# Un_GPS.net
KiCad netlist of a schematic drawn in EAGLE
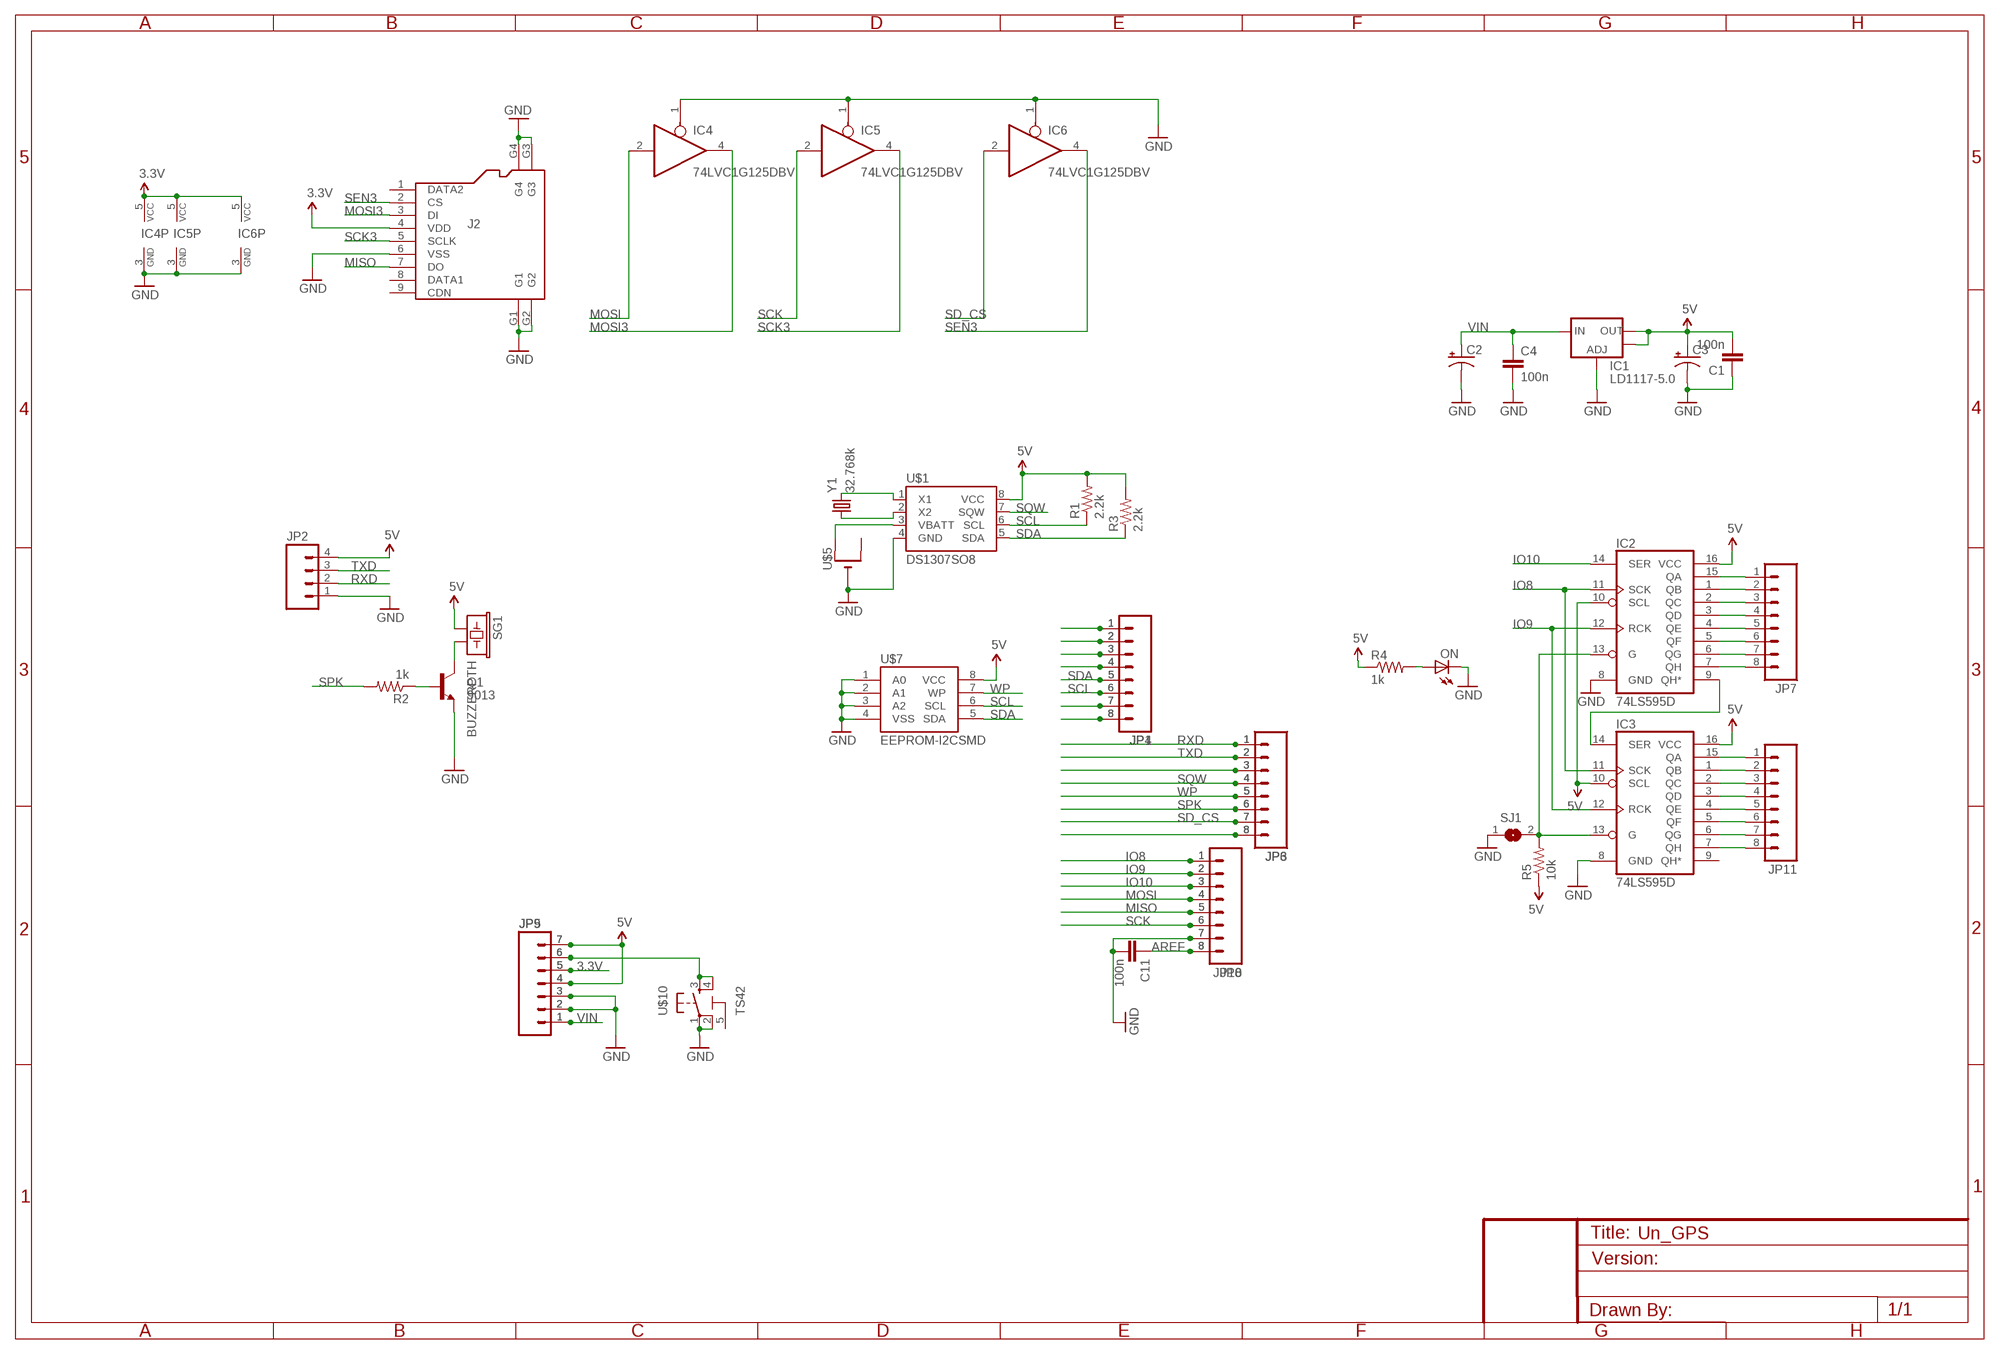
[diagram p0: schematic, sheet 1]

(export (version "E")
  (design (tool "Eeschema 10.0.6"))
  (components
    (comp (ref "C1")
      (value "100n")
      (footprint "eagle-import:0603-CAP")
      (libsource (lib "eagle-import") (part "CAP0603-CAP"))
    )
    (comp (ref "C2")
      (value "CAP_POL1206")
      (footprint "eagle-import:EIA3216")
      (libsource (lib "eagle-import") (part "CAP_POL1206"))
    )
    (comp (ref "C3")
      (value "CAP_POL1206")
      (footprint "eagle-import:EIA3216")
      (libsource (lib "eagle-import") (part "CAP_POL1206"))
    )
    (comp (ref "C4")
      (value "100n")
      (footprint "eagle-import:0603-CAP")
      (libsource (lib "eagle-import") (part "CAP0603-CAP"))
    )
    (comp (ref "C11")
      (value "100n")
      (footprint "eagle-import:0603-CAP")
      (libsource (lib "eagle-import") (part "CAP0603-CAP"))
    )
    (comp (ref "IC1")
      (value "LD1117-5.0")
      (footprint "eagle-import:SOT223")
      (libsource (lib "eagle-import") (part "V_REG_LM1117SOT223"))
    )
    (comp (ref "IC2")
      (value "74LS595D")
      (footprint "eagle-import:SO16")
      (libsource (lib "eagle-import") (part "74595DLS"))
    )
    (comp (ref "IC3")
      (value "74LS595D")
      (footprint "eagle-import:SO16")
      (libsource (lib "eagle-import") (part "74595DLS"))
    )
    (comp (ref "IC4")
      (value "74LVC1G125DBV")
      (footprint "eagle-import:SOT23-5")
      (libsource (lib "eagle-import") (part "741G125DBVLVC"))
    )
    (comp (ref "IC5")
      (value "74LVC1G125DBV")
      (footprint "eagle-import:SOT23-5")
      (libsource (lib "eagle-import") (part "741G125DBVLVC"))
    )
    (comp (ref "IC6")
      (value "74LVC1G125DBV")
      (footprint "eagle-import:SOT23-5")
      (libsource (lib "eagle-import") (part "741G125DBVLVC"))
    )
    (comp (ref "J2")
      (value "HOLDER-MICROSD-9P")
      (footprint "eagle-import:9P-SMD-W_-RING")
      (libsource (lib "eagle-import") (part "HOLDER-MICROSD-9P"))
    )
    (comp (ref "JP1")
      (value "M081X08")
      (footprint "eagle-import:1X08")
      (libsource (lib "eagle-import") (part "M081X08"))
    )
    (comp (ref "JP2")
      (value "M04PTH")
      (footprint "eagle-import:1X04")
      (libsource (lib "eagle-import") (part "M04PTH"))
    )
    (comp (ref "JP3")
      (value "M08")
      (footprint "eagle-import:1X08")
      (libsource (lib "eagle-import") (part "M08"))
    )
    (comp (ref "JP4")
      (value "M081X08")
      (footprint "eagle-import:1X08")
      (libsource (lib "eagle-import") (part "M081X08"))
    )
    (comp (ref "JP5")
      (value "M07")
      (footprint "eagle-import:1X07")
      (libsource (lib "eagle-import") (part "M07"))
    )
    (comp (ref "JP6")
      (value "M08")
      (footprint "eagle-import:1X08")
      (libsource (lib "eagle-import") (part "M08"))
    )
    (comp (ref "JP7")
      (value "M081X08")
      (footprint "eagle-import:1X08")
      (libsource (lib "eagle-import") (part "M081X08"))
    )
    (comp (ref "JP8")
      (value "M08")
      (footprint "eagle-import:1X08")
      (libsource (lib "eagle-import") (part "M08"))
    )
    (comp (ref "JP9")
      (value "M07")
      (footprint "eagle-import:1X07")
      (libsource (lib "eagle-import") (part "M07"))
    )
    (comp (ref "JP10")
      (value "M08")
      (footprint "eagle-import:1X08")
      (libsource (lib "eagle-import") (part "M08"))
    )
    (comp (ref "JP11")
      (value "M081X08")
      (footprint "eagle-import:1X08")
      (libsource (lib "eagle-import") (part "M081X08"))
    )
    (comp (ref "ON")
      (value "LED0805")
      (footprint "eagle-import:LED-0805")
      (libsource (lib "eagle-import") (part "LED0805"))
    )
    (comp (ref "Q1")
      (value "9013")
      (footprint "eagle-import:SOT23-3")
      (libsource (lib "eagle-import") (part "TRANSISTOR_NPNSOT23-3"))
    )
    (comp (ref "R1")
      (value "2.2k")
      (footprint "eagle-import:0805")
      (libsource (lib "eagle-import") (part "RESISTOR0805-RES"))
    )
    (comp (ref "R2")
      (value "1k")
      (footprint "eagle-import:0805")
      (libsource (lib "eagle-import") (part "RESISTOR0805-RES"))
    )
    (comp (ref "R3")
      (value "2.2k")
      (footprint "eagle-import:0805")
      (libsource (lib "eagle-import") (part "RESISTOR0805-RES"))
    )
    (comp (ref "R4")
      (value "1k")
      (footprint "eagle-import:0805")
      (libsource (lib "eagle-import") (part "RESISTOR0805-RES"))
    )
    (comp (ref "R5")
      (value "10k")
      (footprint "eagle-import:0805")
      (libsource (lib "eagle-import") (part "RESISTOR0805-RES"))
    )
    (comp (ref "SG1")
      (value "BUZZERPTH")
      (footprint "eagle-import:BUZZER-12MM")
      (libsource (lib "eagle-import") (part "BUZZERPTH"))
    )
    (comp (ref "SJ1") (value "SJ") (footprint "eagle-import:SJ") (libsource (lib "eagle-import") (part "SJ")))
    (comp (ref "U$1")
      (value "DS1307SO8")
      (footprint "eagle-import:SO08")
      (libsource (lib "eagle-import") (part "DS1307SO8"))
    )
    (comp (ref "U$5")
      (value "CR1220THM")
      (footprint "eagle-import:CR1220-THM")
      (libsource (lib "eagle-import") (part "CR1220THM"))
    )
    (comp (ref "U$7")
      (value "EEPROM-I2CSMD")
      (footprint "eagle-import:SO08")
      (libsource (lib "eagle-import") (part "EEPROM-I2CSMD"))
    )
    (comp (ref "U$10")
      (value "TS42")
      (footprint "eagle-import:TS42")
      (libsource (lib "eagle-import") (part "TS42"))
    )
    (comp (ref "Y1")
      (value "32.768k")
      (footprint "eagle-import:TC26H")
      (libsource (lib "eagle-import") (part "CRYSTALTC26H"))
    )
  )
  (nets
    (net (code "1") (name "/AREF") (class "Default")
      (node (ref "C11") (pin "1") (pinfunction "1_1") (pintype "passive"))
      (node (ref "JP10") (pin "8") (pinfunction "8_8") (pintype "passive"))
      (node (ref "JP8") (pin "8") (pinfunction "8_8") (pintype "passive"))
    )
    (net (code "2") (name "/IO8") (class "Default")
      (node (ref "IC2") (pin "11") (pinfunction "SCK_11") (pintype "input"))
      (node (ref "IC3") (pin "11") (pinfunction "SCK_11") (pintype "input"))
      (node (ref "JP10") (pin "1") (pinfunction "1_1") (pintype "passive"))
      (node (ref "JP8") (pin "1") (pinfunction "1_1") (pintype "passive"))
    )
    (net (code "3") (name "/IO9") (class "Default")
      (node (ref "IC2") (pin "12") (pinfunction "RCK_12") (pintype "input"))
      (node (ref "IC3") (pin "12") (pinfunction "RCK_12") (pintype "input"))
      (node (ref "JP10") (pin "2") (pinfunction "2_2") (pintype "passive"))
      (node (ref "JP8") (pin "2") (pinfunction "2_2") (pintype "passive"))
    )
    (net (code "4") (name "/IO10") (class "Default")
      (node (ref "IC2") (pin "14") (pinfunction "SER_14") (pintype "input"))
      (node (ref "JP10") (pin "3") (pinfunction "3_3") (pintype "passive"))
      (node (ref "JP8") (pin "3") (pinfunction "3_3") (pintype "passive"))
    )
    (net (code "5") (name "/MISO") (class "Default")
      (node (ref "J2") (pin "7") (pinfunction "DO_7") (pintype "bidirectional"))
      (node (ref "JP10") (pin "5") (pinfunction "5_5") (pintype "passive"))
      (node (ref "JP8") (pin "5") (pinfunction "5_5") (pintype "passive"))
    )
    (net (code "6") (name "/MOSI") (class "Default")
      (node (ref "IC4") (pin "2") (pinfunction "I_2") (pintype "input"))
      (node (ref "JP10") (pin "4") (pinfunction "4_4") (pintype "passive"))
      (node (ref "JP8") (pin "4") (pinfunction "4_4") (pintype "passive"))
    )
    (net (code "7") (name "/MOSI3") (class "Default")
      (node (ref "IC4") (pin "4") (pinfunction "O_4") (pintype "tri_state"))
      (node (ref "J2") (pin "3") (pinfunction "DI_3") (pintype "bidirectional"))
    )
    (net (code "8") (name "/RXD") (class "Default")
      (node (ref "JP2") (pin "2") (pinfunction "2_2") (pintype "passive"))
      (node (ref "JP3") (pin "1") (pinfunction "1_1") (pintype "passive"))
      (node (ref "JP6") (pin "1") (pinfunction "1_1") (pintype "passive"))
    )
    (net (code "9") (name "/SCK") (class "Default")
      (node (ref "IC5") (pin "2") (pinfunction "I_2") (pintype "input"))
      (node (ref "JP10") (pin "6") (pinfunction "6_6") (pintype "passive"))
      (node (ref "JP8") (pin "6") (pinfunction "6_6") (pintype "passive"))
    )
    (net (code "10") (name "/SCK3") (class "Default")
      (node (ref "IC5") (pin "4") (pinfunction "O_4") (pintype "tri_state"))
      (node (ref "J2") (pin "5") (pinfunction "SCLK_5") (pintype "bidirectional"))
    )
    (net (code "11") (name "/SCL") (class "Default")
      (node (ref "JP1") (pin "6") (pinfunction "6_6") (pintype "passive"))
      (node (ref "JP4") (pin "6") (pinfunction "6_6") (pintype "passive"))
      (node (ref "R1") (pin "1") (pinfunction "1_1") (pintype "passive"))
      (node (ref "U$1") (pin "6") (pinfunction "SCL_6") (pintype "bidirectional"))
      (node (ref "U$7") (pin "6") (pinfunction "SCL_6") (pintype "bidirectional"))
    )
    (net (code "12") (name "/SDA") (class "Default")
      (node (ref "JP1") (pin "5") (pinfunction "5_5") (pintype "passive"))
      (node (ref "JP4") (pin "5") (pinfunction "5_5") (pintype "passive"))
      (node (ref "R3") (pin "1") (pinfunction "1_1") (pintype "passive"))
      (node (ref "U$1") (pin "5") (pinfunction "SDA_5") (pintype "bidirectional"))
      (node (ref "U$7") (pin "5") (pinfunction "SDA_5") (pintype "bidirectional"))
    )
    (net (code "13") (name "/SD_CS") (class "Default")
      (node (ref "IC6") (pin "2") (pinfunction "I_2") (pintype "input"))
      (node (ref "JP3") (pin "7") (pinfunction "7_7") (pintype "passive"))
      (node (ref "JP6") (pin "7") (pinfunction "7_7") (pintype "passive"))
    )
    (net (code "14") (name "/SEN3") (class "Default")
      (node (ref "IC6") (pin "4") (pinfunction "O_4") (pintype "tri_state"))
      (node (ref "J2") (pin "2") (pinfunction "CS_2") (pintype "bidirectional"))
    )
    (net (code "15") (name "/SPK") (class "Default")
      (node (ref "JP3") (pin "6") (pinfunction "6_6") (pintype "passive"))
      (node (ref "JP6") (pin "6") (pinfunction "6_6") (pintype "passive"))
      (node (ref "R2") (pin "2") (pinfunction "2_2") (pintype "passive"))
    )
    (net (code "16") (name "/SQW") (class "Default")
      (node (ref "JP3") (pin "4") (pinfunction "4_4") (pintype "passive"))
      (node (ref "JP6") (pin "4") (pinfunction "4_4") (pintype "passive"))
      (node (ref "U$1") (pin "7") (pinfunction "SQW_7") (pintype "bidirectional"))
    )
    (net (code "17") (name "/TXD") (class "Default")
      (node (ref "JP2") (pin "3") (pinfunction "3_3") (pintype "passive"))
      (node (ref "JP3") (pin "2") (pinfunction "2_2") (pintype "passive"))
      (node (ref "JP6") (pin "2") (pinfunction "2_2") (pintype "passive"))
    )
    (net (code "18") (name "/VIN") (class "Default")
      (node (ref "C2") (pin "A") (pinfunction "+_A") (pintype "passive"))
      (node (ref "C4") (pin "1") (pinfunction "1_1") (pintype "passive"))
      (node (ref "IC1") (pin "3") (pinfunction "IN_3") (pintype "input"))
      (node (ref "JP5") (pin "1") (pinfunction "1_1") (pintype "passive"))
      (node (ref "JP9") (pin "1") (pinfunction "1_1") (pintype "passive"))
    )
    (net (code "19") (name "/WP") (class "Default")
      (node (ref "JP3") (pin "5") (pinfunction "5_5") (pintype "passive"))
      (node (ref "JP6") (pin "5") (pinfunction "5_5") (pintype "passive"))
      (node (ref "U$7") (pin "7") (pinfunction "WP_7") (pintype "bidirectional"))
    )
    (net (code "20") (name "3.3V") (class "Default")
      (node (ref "IC4") (pin "5") (pinfunction "VCC_5") (pintype "power_in"))
      (node (ref "IC5") (pin "5") (pinfunction "VCC_5") (pintype "power_in"))
      (node (ref "IC6") (pin "5") (pinfunction "VCC_5") (pintype "power_in"))
      (node (ref "J2") (pin "4") (pinfunction "VDD_4") (pintype "bidirectional"))
      (node (ref "JP5") (pin "5") (pinfunction "5_5") (pintype "passive"))
      (node (ref "JP9") (pin "5") (pinfunction "5_5") (pintype "passive"))
    )
    (net (code "21") (name "5V") (class "Default")
      (node (ref "C1") (pin "2") (pinfunction "2_2") (pintype "passive"))
      (node (ref "C3") (pin "A") (pinfunction "+_A") (pintype "passive"))
      (node (ref "IC1") (pin "2") (pinfunction "OUT_2") (pintype "output"))
      (node (ref "IC1") (pin "4") (pinfunction "OUT_4") (pintype "output"))
      (node (ref "IC2") (pin "10") (pinfunction "SCL_10") (pintype "input"))
      (node (ref "IC2") (pin "16") (pinfunction "VCC_16") (pintype "power_in"))
      (node (ref "IC3") (pin "10") (pinfunction "SCL_10") (pintype "input"))
      (node (ref "IC3") (pin "16") (pinfunction "VCC_16") (pintype "power_in"))
      (node (ref "JP2") (pin "4") (pinfunction "4_4") (pintype "passive"))
      (node (ref "JP5") (pin "4") (pinfunction "4_4") (pintype "passive"))
      (node (ref "JP5") (pin "7") (pinfunction "7_7") (pintype "passive"))
      (node (ref "JP9") (pin "4") (pinfunction "4_4") (pintype "passive"))
      (node (ref "JP9") (pin "7") (pinfunction "7_7") (pintype "passive"))
      (node (ref "R1") (pin "2") (pinfunction "2_2") (pintype "passive"))
      (node (ref "R3") (pin "2") (pinfunction "2_2") (pintype "passive"))
      (node (ref "R4") (pin "1") (pinfunction "1_1") (pintype "passive"))
      (node (ref "R5") (pin "1") (pinfunction "1_1") (pintype "passive"))
      (node (ref "SG1") (pin "+") (pinfunction "1_+") (pintype "passive"))
      (node (ref "U$1") (pin "8") (pinfunction "VCC_8") (pintype "bidirectional"))
      (node (ref "U$7") (pin "8") (pinfunction "VCC_8") (pintype "power_in"))
    )
    (net (code "22") (name "GND") (class "Default")
      (node (ref "C1") (pin "1") (pinfunction "1_1") (pintype "passive"))
      (node (ref "C11") (pin "2") (pinfunction "2_2") (pintype "passive"))
      (node (ref "C2") (pin "C") (pinfunction "-_C") (pintype "passive"))
      (node (ref "C3") (pin "C") (pinfunction "-_C") (pintype "passive"))
      (node (ref "C4") (pin "2") (pinfunction "2_2") (pintype "passive"))
      (node (ref "IC1") (pin "1") (pinfunction "ADJ_1") (pintype "input"))
      (node (ref "IC2") (pin "8") (pinfunction "GND_8") (pintype "power_in"))
      (node (ref "IC3") (pin "8") (pinfunction "GND_8") (pintype "power_in"))
      (node (ref "IC4") (pin "1") (pinfunction "OE_1") (pintype "input"))
      (node (ref "IC4") (pin "3") (pinfunction "GND_3") (pintype "power_in"))
      (node (ref "IC5") (pin "1") (pinfunction "OE_1") (pintype "input"))
      (node (ref "IC5") (pin "3") (pinfunction "GND_3") (pintype "power_in"))
      (node (ref "IC6") (pin "1") (pinfunction "OE_1") (pintype "input"))
      (node (ref "IC6") (pin "3") (pinfunction "GND_3") (pintype "power_in"))
      (node (ref "J2") (pin "6") (pinfunction "VSS_6") (pintype "bidirectional"))
      (node (ref "J2") (pin "G1") (pinfunction "G1_G1") (pintype "bidirectional"))
      (node (ref "J2") (pin "G2") (pinfunction "G2_G2") (pintype "bidirectional"))
      (node (ref "J2") (pin "G3") (pinfunction "G3_G3") (pintype "bidirectional"))
      (node (ref "J2") (pin "G4") (pinfunction "G4_G4") (pintype "bidirectional"))
      (node (ref "JP10") (pin "7") (pinfunction "7_7") (pintype "passive"))
      (node (ref "JP2") (pin "1") (pinfunction "1_1") (pintype "passive"))
      (node (ref "JP5") (pin "2") (pinfunction "2_2") (pintype "passive"))
      (node (ref "JP5") (pin "3") (pinfunction "3_3") (pintype "passive"))
      (node (ref "JP8") (pin "7") (pinfunction "7_7") (pintype "passive"))
      (node (ref "JP9") (pin "2") (pinfunction "2_2") (pintype "passive"))
      (node (ref "JP9") (pin "3") (pinfunction "3_3") (pintype "passive"))
      (node (ref "ON") (pin "2") (pinfunction "C_2") (pintype "passive"))
      (node (ref "Q1") (pin "2") (pinfunction "E_2") (pintype "passive"))
      (node (ref "SJ1") (pin "1") (pinfunction "1_1") (pintype "passive"))
      (node (ref "U$1") (pin "4") (pinfunction "GND_4") (pintype "bidirectional"))
      (node (ref "U$10") (pin "1") (pinfunction "1_1") (pintype "passive"))
      (node (ref "U$10") (pin "2") (pinfunction "2_2") (pintype "passive"))
      (node (ref "U$5") (pin "-") (pinfunction "-_-") (pintype "passive"))
      (node (ref "U$7") (pin "1") (pinfunction "A0_1") (pintype "bidirectional"))
      (node (ref "U$7") (pin "2") (pinfunction "A1_2") (pintype "bidirectional"))
      (node (ref "U$7") (pin "3") (pinfunction "A2_3") (pintype "bidirectional"))
      (node (ref "U$7") (pin "4") (pinfunction "VSS_4") (pintype "power_in"))
    )
    (net (code "23") (name "Net-(IC2-G)") (class "Default")
      (node (ref "IC2") (pin "13") (pinfunction "G_13") (pintype "input"))
      (node (ref "IC3") (pin "13") (pinfunction "G_13") (pintype "input"))
      (node (ref "R5") (pin "2") (pinfunction "2_2") (pintype "passive"))
      (node (ref "SJ1") (pin "2") (pinfunction "2_2") (pintype "passive"))
    )
    (net (code "24") (name "Net-(IC2-QA)") (class "Default")
      (node (ref "IC2") (pin "15") (pinfunction "QA_15") (pintype "tri_state"))
      (node (ref "JP7") (pin "1") (pinfunction "1_1") (pintype "passive"))
    )
    (net (code "25") (name "Net-(IC2-QB)") (class "Default")
      (node (ref "IC2") (pin "1") (pinfunction "QB_1") (pintype "tri_state"))
      (node (ref "JP7") (pin "2") (pinfunction "2_2") (pintype "passive"))
    )
    (net (code "26") (name "Net-(IC2-QC)") (class "Default")
      (node (ref "IC2") (pin "2") (pinfunction "QC_2") (pintype "tri_state"))
      (node (ref "JP7") (pin "3") (pinfunction "3_3") (pintype "passive"))
    )
    (net (code "27") (name "Net-(IC2-QD)") (class "Default")
      (node (ref "IC2") (pin "3") (pinfunction "QD_3") (pintype "tri_state"))
      (node (ref "JP7") (pin "4") (pinfunction "4_4") (pintype "passive"))
    )
    (net (code "28") (name "Net-(IC2-QE)") (class "Default")
      (node (ref "IC2") (pin "4") (pinfunction "QE_4") (pintype "tri_state"))
      (node (ref "JP7") (pin "5") (pinfunction "5_5") (pintype "passive"))
    )
    (net (code "29") (name "Net-(IC2-QF)") (class "Default")
      (node (ref "IC2") (pin "5") (pinfunction "QF_5") (pintype "tri_state"))
      (node (ref "JP7") (pin "6") (pinfunction "6_6") (pintype "passive"))
    )
    (net (code "30") (name "Net-(IC2-QG)") (class "Default")
      (node (ref "IC2") (pin "6") (pinfunction "QG_6") (pintype "tri_state"))
      (node (ref "JP7") (pin "7") (pinfunction "7_7") (pintype "passive"))
    )
    (net (code "31") (name "Net-(IC2-QH)") (class "Default")
      (node (ref "IC2") (pin "7") (pinfunction "QH_7") (pintype "tri_state"))
      (node (ref "JP7") (pin "8") (pinfunction "8_8") (pintype "passive"))
    )
    (net (code "32") (name "Net-(IC2-QH*)") (class "Default")
      (node (ref "IC2") (pin "9") (pinfunction "QH*_9") (pintype "tri_state"))
      (node (ref "IC3") (pin "14") (pinfunction "SER_14") (pintype "input"))
    )
    (net (code "33") (name "Net-(IC3-QA)") (class "Default")
      (node (ref "IC3") (pin "15") (pinfunction "QA_15") (pintype "tri_state"))
      (node (ref "JP11") (pin "1") (pinfunction "1_1") (pintype "passive"))
    )
    (net (code "34") (name "Net-(IC3-QB)") (class "Default")
      (node (ref "IC3") (pin "1") (pinfunction "QB_1") (pintype "tri_state"))
      (node (ref "JP11") (pin "2") (pinfunction "2_2") (pintype "passive"))
    )
    (net (code "35") (name "Net-(IC3-QC)") (class "Default")
      (node (ref "IC3") (pin "2") (pinfunction "QC_2") (pintype "tri_state"))
      (node (ref "JP11") (pin "3") (pinfunction "3_3") (pintype "passive"))
    )
    (net (code "36") (name "Net-(IC3-QD)") (class "Default")
      (node (ref "IC3") (pin "3") (pinfunction "QD_3") (pintype "tri_state"))
      (node (ref "JP11") (pin "4") (pinfunction "4_4") (pintype "passive"))
    )
    (net (code "37") (name "Net-(IC3-QE)") (class "Default")
      (node (ref "IC3") (pin "4") (pinfunction "QE_4") (pintype "tri_state"))
      (node (ref "JP11") (pin "5") (pinfunction "5_5") (pintype "passive"))
    )
    (net (code "38") (name "Net-(IC3-QF)") (class "Default")
      (node (ref "IC3") (pin "5") (pinfunction "QF_5") (pintype "tri_state"))
      (node (ref "JP11") (pin "6") (pinfunction "6_6") (pintype "passive"))
    )
    (net (code "39") (name "Net-(IC3-QG)") (class "Default")
      (node (ref "IC3") (pin "6") (pinfunction "QG_6") (pintype "tri_state"))
      (node (ref "JP11") (pin "7") (pinfunction "7_7") (pintype "passive"))
    )
    (net (code "40") (name "Net-(IC3-QH)") (class "Default")
      (node (ref "IC3") (pin "7") (pinfunction "QH_7") (pintype "tri_state"))
      (node (ref "JP11") (pin "8") (pinfunction "8_8") (pintype "passive"))
    )
    (net (code "41") (name "Net-(JP1-Pad1)") (class "Default")
      (node (ref "JP1") (pin "1") (pinfunction "1_1") (pintype "passive"))
      (node (ref "JP4") (pin "1") (pinfunction "1_1") (pintype "passive"))
    )
    (net (code "42") (name "Net-(JP1-Pad2)") (class "Default")
      (node (ref "JP1") (pin "2") (pinfunction "2_2") (pintype "passive"))
      (node (ref "JP4") (pin "2") (pinfunction "2_2") (pintype "passive"))
    )
    (net (code "43") (name "Net-(JP1-Pad3)") (class "Default")
      (node (ref "JP1") (pin "3") (pinfunction "3_3") (pintype "passive"))
      (node (ref "JP4") (pin "3") (pinfunction "3_3") (pintype "passive"))
    )
    (net (code "44") (name "Net-(JP1-Pad4)") (class "Default")
      (node (ref "JP1") (pin "4") (pinfunction "4_4") (pintype "passive"))
      (node (ref "JP4") (pin "4") (pinfunction "4_4") (pintype "passive"))
    )
    (net (code "45") (name "Net-(JP1-Pad7)") (class "Default")
      (node (ref "JP1") (pin "7") (pinfunction "7_7") (pintype "passive"))
      (node (ref "JP4") (pin "7") (pinfunction "7_7") (pintype "passive"))
    )
    (net (code "46") (name "Net-(JP1-Pad8)") (class "Default")
      (node (ref "JP1") (pin "8") (pinfunction "8_8") (pintype "passive"))
      (node (ref "JP4") (pin "8") (pinfunction "8_8") (pintype "passive"))
    )
    (net (code "47") (name "Net-(JP3-Pad3)") (class "Default")
      (node (ref "JP3") (pin "3") (pinfunction "3_3") (pintype "passive"))
      (node (ref "JP6") (pin "3") (pinfunction "3_3") (pintype "passive"))
    )
    (net (code "48") (name "Net-(JP3-Pad8)") (class "Default")
      (node (ref "JP3") (pin "8") (pinfunction "8_8") (pintype "passive"))
      (node (ref "JP6") (pin "8") (pinfunction "8_8") (pintype "passive"))
    )
    (net (code "49") (name "Net-(JP5-Pad6)") (class "Default")
      (node (ref "JP5") (pin "6") (pinfunction "6_6") (pintype "passive"))
      (node (ref "JP9") (pin "6") (pinfunction "6_6") (pintype "passive"))
      (node (ref "U$10") (pin "3") (pinfunction "3_3") (pintype "passive"))
      (node (ref "U$10") (pin "4") (pinfunction "4_4") (pintype "passive"))
    )
    (net (code "50") (name "Net-(ON-A)") (class "Default")
      (node (ref "ON") (pin "1") (pinfunction "A_1") (pintype "passive"))
      (node (ref "R4") (pin "2") (pinfunction "2_2") (pintype "passive"))
    )
    (net (code "51") (name "Net-(Q1-B)") (class "Default")
      (node (ref "Q1") (pin "1") (pinfunction "B_1") (pintype "passive"))
      (node (ref "R2") (pin "1") (pinfunction "1_1") (pintype "passive"))
    )
    (net (code "52") (name "Net-(Q1-C)") (class "Default")
      (node (ref "Q1") (pin "3") (pinfunction "C_3") (pintype "passive"))
      (node (ref "SG1") (pin "-") (pinfunction "2_-") (pintype "passive"))
    )
    (net (code "53") (name "Net-(U$1-VBATT)") (class "Default")
      (node (ref "U$1") (pin "3") (pinfunction "VBATT_3") (pintype "bidirectional"))
      (node (ref "U$5") (pin "+1") (pinfunction "+_+1") (pintype "passive"))
    )
    (net (code "54") (name "Net-(U$1-X1)") (class "Default")
      (node (ref "U$1") (pin "1") (pinfunction "X1_1") (pintype "bidirectional"))
      (node (ref "Y1") (pin "2") (pinfunction "2_2") (pintype "passive"))
    )
    (net (code "55") (name "Net-(U$1-X2)") (class "Default")
      (node (ref "U$1") (pin "2") (pinfunction "X2_2") (pintype "bidirectional"))
      (node (ref "Y1") (pin "1") (pinfunction "1_1") (pintype "passive"))
    )
    (net (code "56") (name "unconnected-(IC3-QH*-Pad9)") (class "Default")
      (node (ref "IC3") (pin "9") (pinfunction "QH*_9") (pintype "tri_state"))
    )
    (net (code "57") (name "unconnected-(J2-CDN-Pad9)") (class "Default")
      (node (ref "J2") (pin "9") (pinfunction "CDN_9") (pintype "bidirectional"))
    )
    (net (code "58") (name "unconnected-(J2-DATA1-Pad8)") (class "Default")
      (node (ref "J2") (pin "8") (pinfunction "DATA1_8") (pintype "bidirectional"))
    )
    (net (code "59") (name "unconnected-(J2-DATA2-Pad1)") (class "Default")
      (node (ref "J2") (pin "1") (pinfunction "DATA2_1") (pintype "bidirectional"))
    )
    (net (code "60") (name "unconnected-(U$5-+1-Pad+2)") (class "Default")
      (node (ref "U$5") (pin "+2") (pinfunction "+1_+2") (pintype "passive"))
    )
    (net (code "61") (name "unconnected-(U$10-Pad5)") (class "Default")
      (node (ref "U$10") (pin "5") (pinfunction "5_5") (pintype "passive"))
    )
  )
)
